# Display.net
KiCad netlist of a schematic drawn in EAGLE
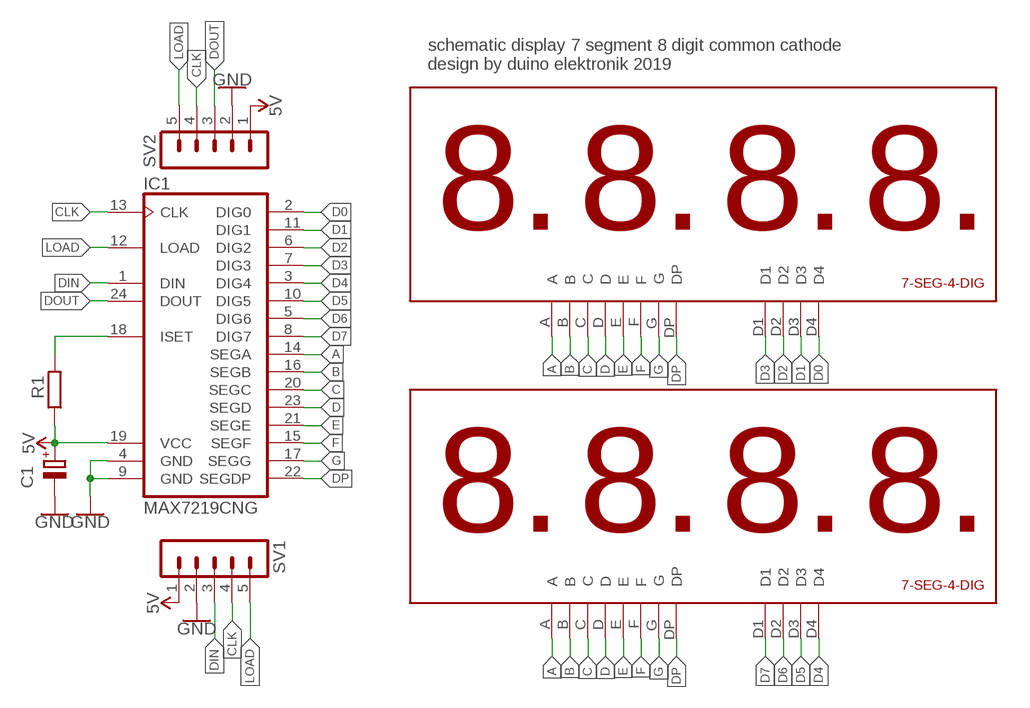
[diagram p0: schematic, sheet 1]

(export (version "E")
  (design (tool "Eeschema 10.0.6"))
  (components
    (comp (ref "C1")
      (value "CPOL-EUE1.8-4")
      (footprint "eagle-import:E1,8-4")
      (libsource (lib "eagle-import") (part "CPOL-EUE1.8-4"))
    )
    (comp (ref "IC1")
      (value "MAX7219CNG")
      (footprint "eagle-import:DIL24-3")
      (fields (field (name "MF") "MAXIM"))
      (libsource (lib "eagle-import") (part "MAX7219CNG"))
    )
    (comp (ref "R1")
      (value "R-EU_0207/10")
      (footprint "eagle-import:0207_10")
      (libsource (lib "eagle-import") (part "R-EU_0207/10"))
    )
    (comp (ref "SV1")
      (value "MA05-1")
      (footprint "eagle-import:MA05-1")
      (libsource (lib "eagle-import") (part "MA05-1"))
    )
    (comp (ref "SV2")
      (value "MA05-1")
      (footprint "eagle-import:MA05-1")
      (libsource (lib "eagle-import") (part "MA05-1"))
    )
    (comp (ref "U$1")
      (value "7-SEG-4-DIG7-SEG-4-DIG")
      (footprint "eagle-import:7-SEG-4-DIG")
      (libsource (lib "eagle-import") (part "7-SEG-4-DIG7-SEG-4-DIG"))
    )
    (comp (ref "U$2")
      (value "7-SEG-4-DIG7-SEG-4-DIG")
      (footprint "eagle-import:7-SEG-4-DIG")
      (libsource (lib "eagle-import") (part "7-SEG-4-DIG7-SEG-4-DIG"))
    )
  )
  (nets
    (net (code "1") (name "5V") (class "Default")
      (node (ref "C1") (pin "+") (pinfunction "+_+") (pintype "passive"))
      (node (ref "IC1") (pin "19") (pinfunction "VCC_19") (pintype "power_in"))
      (node (ref "R1") (pin "1") (pinfunction "1_1") (pintype "passive"))
      (node (ref "SV1") (pin "1") (pinfunction "1_1") (pintype "passive"))
      (node (ref "SV2") (pin "1") (pinfunction "1_1") (pintype "passive"))
    )
    (net (code "2") (name "A") (class "Default")
      (node (ref "IC1") (pin "14") (pinfunction "SEGA_14") (pintype "output"))
      (node (ref "U$1") (pin "A") (pinfunction "A_A") (pintype "bidirectional"))
      (node (ref "U$2") (pin "A") (pinfunction "A_A") (pintype "bidirectional"))
    )
    (net (code "3") (name "B") (class "Default")
      (node (ref "IC1") (pin "16") (pinfunction "SEGB_16") (pintype "output"))
      (node (ref "U$1") (pin "B") (pinfunction "B_B") (pintype "bidirectional"))
      (node (ref "U$2") (pin "B") (pinfunction "B_B") (pintype "bidirectional"))
    )
    (net (code "4") (name "C") (class "Default")
      (node (ref "IC1") (pin "20") (pinfunction "SEGC_20") (pintype "output"))
      (node (ref "U$1") (pin "C") (pinfunction "C_C") (pintype "bidirectional"))
      (node (ref "U$2") (pin "C") (pinfunction "C_C") (pintype "bidirectional"))
    )
    (net (code "5") (name "CLK") (class "Default")
      (node (ref "IC1") (pin "13") (pinfunction "CLK_13") (pintype "input"))
      (node (ref "SV1") (pin "4") (pinfunction "4_4") (pintype "passive"))
      (node (ref "SV2") (pin "4") (pinfunction "4_4") (pintype "passive"))
    )
    (net (code "6") (name "D") (class "Default")
      (node (ref "IC1") (pin "23") (pinfunction "SEGD_23") (pintype "output"))
      (node (ref "U$1") (pin "D") (pinfunction "D_D") (pintype "bidirectional"))
      (node (ref "U$2") (pin "D") (pinfunction "D_D") (pintype "bidirectional"))
    )
    (net (code "7") (name "D0") (class "Default")
      (node (ref "IC1") (pin "2") (pinfunction "DIG0_2") (pintype "output"))
      (node (ref "U$1") (pin "D4") (pinfunction "D4_D4") (pintype "bidirectional"))
    )
    (net (code "8") (name "D1") (class "Default")
      (node (ref "IC1") (pin "11") (pinfunction "DIG1_11") (pintype "output"))
      (node (ref "U$1") (pin "D3") (pinfunction "D3_D3") (pintype "bidirectional"))
    )
    (net (code "9") (name "D2") (class "Default")
      (node (ref "IC1") (pin "6") (pinfunction "DIG2_6") (pintype "output"))
      (node (ref "U$1") (pin "D2") (pinfunction "D2_D2") (pintype "bidirectional"))
    )
    (net (code "10") (name "D3") (class "Default")
      (node (ref "IC1") (pin "7") (pinfunction "DIG3_7") (pintype "output"))
      (node (ref "U$1") (pin "D1") (pinfunction "D1_D1") (pintype "bidirectional"))
    )
    (net (code "11") (name "D4") (class "Default")
      (node (ref "IC1") (pin "3") (pinfunction "DIG4_3") (pintype "output"))
      (node (ref "U$2") (pin "D4") (pinfunction "D4_D4") (pintype "bidirectional"))
    )
    (net (code "12") (name "D5") (class "Default")
      (node (ref "IC1") (pin "10") (pinfunction "DIG5_10") (pintype "output"))
      (node (ref "U$2") (pin "D3") (pinfunction "D3_D3") (pintype "bidirectional"))
    )
    (net (code "13") (name "D6") (class "Default")
      (node (ref "IC1") (pin "5") (pinfunction "DIG6_5") (pintype "output"))
      (node (ref "U$2") (pin "D2") (pinfunction "D2_D2") (pintype "bidirectional"))
    )
    (net (code "14") (name "D7") (class "Default")
      (node (ref "IC1") (pin "8") (pinfunction "DIG7_8") (pintype "output"))
      (node (ref "U$2") (pin "D1") (pinfunction "D1_D1") (pintype "bidirectional"))
    )
    (net (code "15") (name "DIN") (class "Default")
      (node (ref "IC1") (pin "1") (pinfunction "DIN_1") (pintype "input"))
      (node (ref "SV1") (pin "3") (pinfunction "3_3") (pintype "passive"))
    )
    (net (code "16") (name "DOUT") (class "Default")
      (node (ref "IC1") (pin "24") (pinfunction "DOUT_24") (pintype "output"))
      (node (ref "SV2") (pin "3") (pinfunction "3_3") (pintype "passive"))
    )
    (net (code "17") (name "DP") (class "Default")
      (node (ref "IC1") (pin "22") (pinfunction "SEGDP_22") (pintype "output"))
      (node (ref "U$1") (pin "DP") (pinfunction "DP_DP") (pintype "bidirectional"))
      (node (ref "U$2") (pin "DP") (pinfunction "DP_DP") (pintype "bidirectional"))
    )
    (net (code "18") (name "E") (class "Default")
      (node (ref "IC1") (pin "21") (pinfunction "SEGE_21") (pintype "output"))
      (node (ref "U$1") (pin "E") (pinfunction "E_E") (pintype "bidirectional"))
      (node (ref "U$2") (pin "E") (pinfunction "E_E") (pintype "bidirectional"))
    )
    (net (code "19") (name "F") (class "Default")
      (node (ref "IC1") (pin "15") (pinfunction "SEGF_15") (pintype "output"))
      (node (ref "U$1") (pin "F") (pinfunction "F_F") (pintype "bidirectional"))
      (node (ref "U$2") (pin "F") (pinfunction "F_F") (pintype "bidirectional"))
    )
    (net (code "20") (name "G") (class "Default")
      (node (ref "IC1") (pin "17") (pinfunction "SEGG_17") (pintype "output"))
      (node (ref "U$1") (pin "G") (pinfunction "G_G") (pintype "bidirectional"))
      (node (ref "U$2") (pin "G") (pinfunction "G_G") (pintype "bidirectional"))
    )
    (net (code "21") (name "GND") (class "Default")
      (node (ref "C1") (pin "-") (pinfunction "-_-") (pintype "passive"))
      (node (ref "IC1") (pin "4") (pinfunction "GND_4") (pintype "power_in"))
      (node (ref "IC1") (pin "9") (pinfunction "GND_9") (pintype "power_in"))
      (node (ref "SV1") (pin "2") (pinfunction "2_2") (pintype "passive"))
      (node (ref "SV2") (pin "2") (pinfunction "2_2") (pintype "passive"))
    )
    (net (code "22") (name "LOAD") (class "Default")
      (node (ref "IC1") (pin "12") (pinfunction "LOAD_12") (pintype "input"))
      (node (ref "SV1") (pin "5") (pinfunction "5_5") (pintype "passive"))
      (node (ref "SV2") (pin "5") (pinfunction "5_5") (pintype "passive"))
    )
    (net (code "23") (name "Net-(IC1-ISET)") (class "Default")
      (node (ref "IC1") (pin "18") (pinfunction "ISET_18") (pintype "input"))
      (node (ref "R1") (pin "2") (pinfunction "2_2") (pintype "passive"))
    )
  )
)
